# Fri3d_2024_Blaster_01.net
KiCad netlist of a schematic drawn in Altium Designer
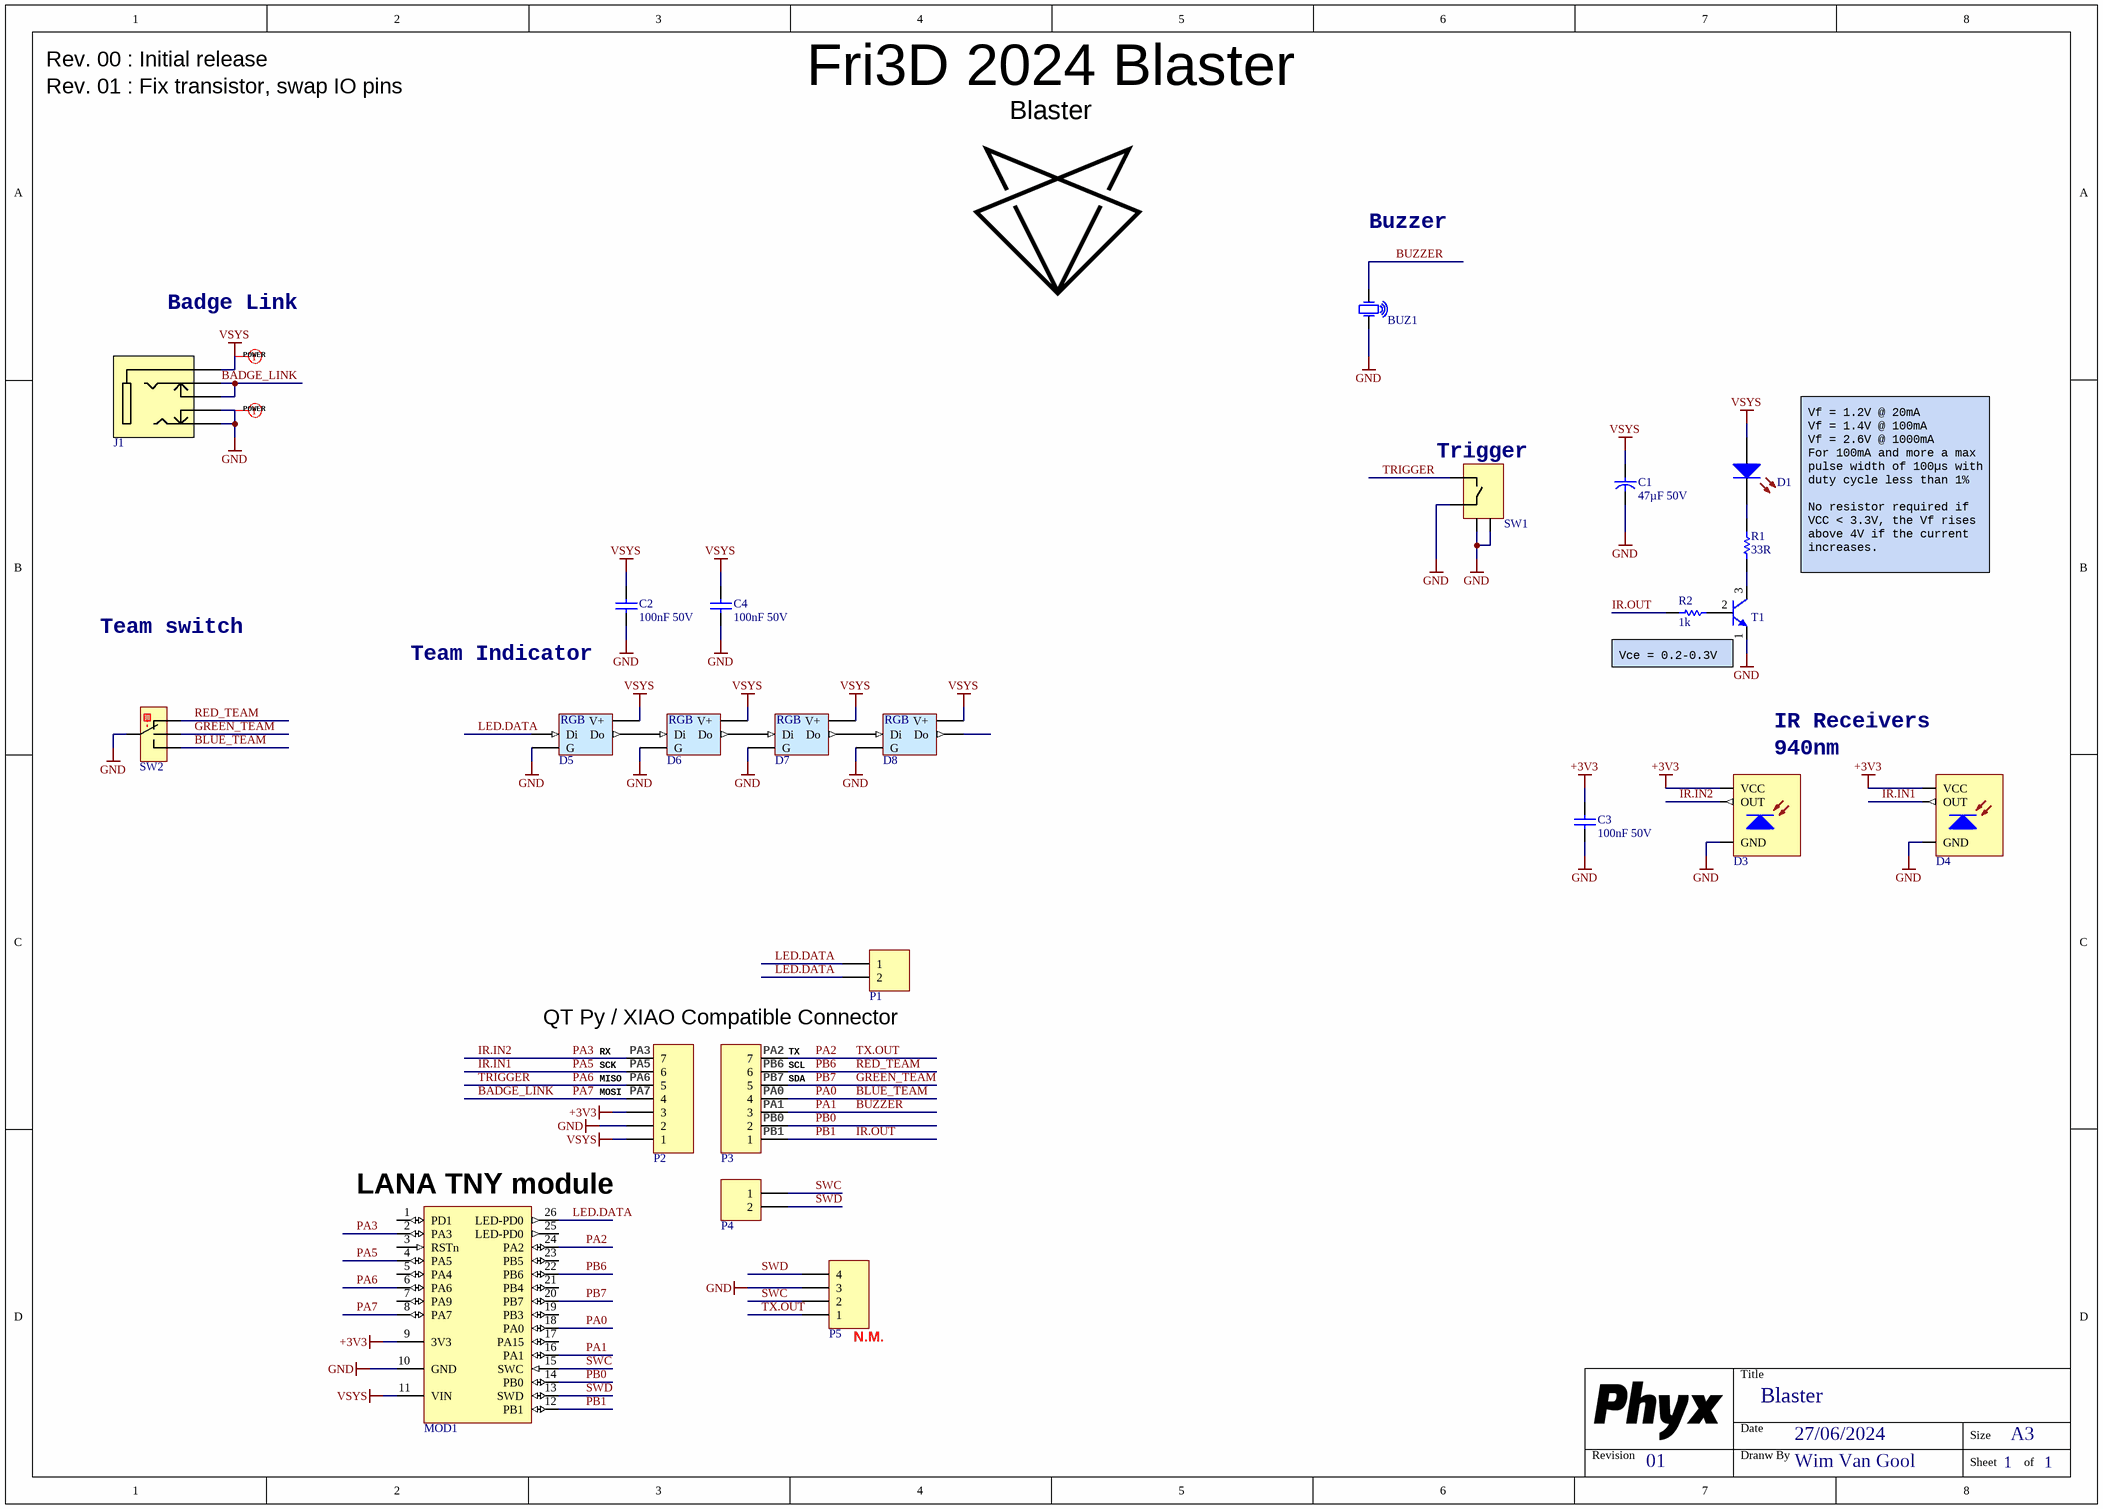
[diagram p0: Fri3d_2024_Blaster_01.SchDoc]

(export (version "E")
  (design (tool "Eeschema 10.0.6"))
  (components
    (comp (ref "BUZ1")
      (value "14x14x7mm Piezo Buzzer Transducer 80dB")
      (footprint "CUI_CEP-1162")
      (description "Crystal Oscillator")
      (libsource (lib "Phyx_Components") (part "Buzzer"))
    )
    (comp (ref "C1")
      (value "47µF 50V")
      (footprint "C_8x9_3.5mm")
      (description "Capacitor electrolyt")
      (fields (field (name "Comment") "CAP_POL"))
      (libsource (lib "Phyx_Components") (part "CAP_POL"))
    )
    (comp (ref "C2")
      (value "100nF 50V")
      (footprint "C_5.08mm")
      (description "Capacitor Ceramic")
      (fields (field (name "Comment") "CAP_CERAMIC"))
      (libsource (lib "Phyx_Components") (part "CAP_CERAMIC"))
    )
    (comp (ref "C3")
      (value "100nF 50V")
      (footprint "C_5.08mm")
      (description "Capacitor Ceramic")
      (fields (field (name "Comment") "CAP_CERAMIC"))
      (libsource (lib "Phyx_Components") (part "CAP_CERAMIC"))
    )
    (comp (ref "C4")
      (value "100nF 50V")
      (footprint "C_5.08mm")
      (description "Capacitor Ceramic")
      (fields (field (name "Comment") "CAP_CERAMIC"))
      (libsource (lib "Phyx_Components") (part "CAP_CERAMIC"))
    )
    (comp (ref "D1")
      (value "5mm IR LED, 940nm, 100mA, 1.35V, 25Deg")
      (footprint "LED_5MM_RD")
      (description "=Description")
      (libsource (lib "Phyx_Components") (part "LED_IR"))
    )
    (comp (ref "D3")
      (value "IRM-3638N3F14 Infrared Receiver 38 kHz 45° 2.7-5.5V")
      (footprint "VIS_TSOP381x_BENT")
      (description "=Description")
      (libsource (lib "Phyx_Components") (part "PHO_IR_TSOP381x"))
    )
    (comp (ref "D4")
      (value "IRM-3638N3F14 Infrared Receiver 38 kHz 45° 2.7-5.5V")
      (footprint "VIS_TSOP381x_BENT")
      (description "=Description")
      (libsource (lib "Phyx_Components") (part "PHO_IR_TSOP381x"))
    )
    (comp (ref "D5")
      (value "WS2812 based digital RGB LED 4020 White package Side emitting")
      (footprint "LED_8mm_RGB_RA_EASY")
      (description "=Description")
      (libsource (lib "Phyx_Components") (part "LED_RGB_WS2812B_5mm"))
    )
    (comp (ref "D6")
      (value "WS2812 based digital RGB LED 4020 White package Side emitting")
      (footprint "LED_8mm_RGB_RA_EASY")
      (description "=Description")
      (libsource (lib "Phyx_Components") (part "LED_RGB_WS2812B_5mm"))
    )
    (comp (ref "D7")
      (value "WS2812 based digital RGB LED 4020 White package Side emitting")
      (footprint "LED_8mm_RGB_RA_EASY")
      (description "=Description")
      (libsource (lib "Phyx_Components") (part "LED_RGB_WS2812B_5mm"))
    )
    (comp (ref "D8")
      (value "WS2812 based digital RGB LED 4020 White package Side emitting")
      (footprint "LED_8mm_RGB_RA_EASY")
      (description "=Description")
      (libsource (lib "Phyx_Components") (part "LED_RGB_WS2812B_5mm"))
    )
    (comp (ref "J1")
      (value "3.5mm jack, dual switch, black, 3 contacts")
      (footprint "CUI_SJ1-3525NG")
      (description "=Description")
      (libsource (lib "Phyx_Components") (part "CUI_SJ1-3525NG"))
    )
    (comp (ref "MOD1")
      (value "CH23V203 based TNY module")
      (footprint "PHYX_LANA_TNY_SMD")
      (libsource (lib "Phyx_Components") (part "PHYX_LANA_TNY_SMD"))
    )
    (comp (ref "P1")
      (value "Header 2")
      (footprint "HDR1X2")
      (libsource (lib "Phyx_Components") (part "Header 2"))
    )
    (comp (ref "P2")
      (value "Header 7")
      (footprint "HDR1X7")
      (libsource (lib "Phyx_Components") (part "Header 7"))
    )
    (comp (ref "P3") (value "Header 7") (footprint "HDR1X7") (libsource (lib "") (part "Header 7_1")))
    (comp (ref "P4") (value "Header 2") (footprint "HDR1X2") (libsource (lib "") (part "Header 2_1")))
    (comp (ref "P5")
      (value "Header 4")
      (footprint "HDR1X4")
      (libsource (lib "Phyx_Components") (part "Header 4"))
    )
    (comp (ref "R1")
      (value "33R")
      (footprint "RES_10mm")
      (fields (field (name "Comment") "RESISTOR"))
      (libsource (lib "Phyx_Components") (part "RESISTOR"))
    )
    (comp (ref "R2")
      (value "1k")
      (footprint "RES_10mm")
      (fields (field (name "Comment") "RESISTOR"))
      (libsource (lib "Phyx_Components") (part "RESISTOR"))
    )
    (comp (ref "SW1")
      (value "Tact switch, RA, 3,85mm")
      (footprint "TACTSW_RA_385")
      (libsource (lib "Phyx_Components") (part "SW_TACT_RA"))
    )
    (comp (ref "SW2")
      (value "1P3T SK13D07VG3 3mm post")
      (footprint "SK13D07VG3")
      (libsource (lib "Phyx_Components") (part "SW_1P3T"))
    )
    (comp (ref "T1")
      (value "0.2A 40V 100hfe NPN Transistor")
      (footprint "TO-92A_WIDE")
      (libsource (lib "Phyx_Components") (part "NPN_EBC"))
    )
  )
  (nets
    (net (code "1") (name "+3V3") (class "Default")
      (node (ref "C3") (pin "1") (pinfunction "1_1") (pintype "passive"))
      (node (ref "D3") (pin "3") (pinfunction "VCC_3") (pintype "power_in"))
      (node (ref "D4") (pin "3") (pinfunction "VCC_3") (pintype "power_in"))
      (node (ref "MOD1") (pin "9") (pinfunction "3V3_9") (pintype "power_in"))
      (node (ref "P2") (pin "3") (pinfunction "3_3") (pintype "passive"))
    )
    (net (code "3") (name "/BADGE_LINK") (class "Default")
      (node (ref "J1") (pin "3") (pinfunction "Ring_3") (pintype "passive"))
      (node (ref "J1") (pin "5") (pinfunction "5_5") (pintype "passive"))
      (node (ref "MOD1") (pin "8") (pinfunction "PA7_8") (pintype "bidirectional"))
      (node (ref "P2") (pin "4") (pinfunction "4_4") (pintype "passive"))
    )
    (net (code "4") (name "/BLUE_TEAM") (class "Default")
      (node (ref "MOD1") (pin "18") (pinfunction "PA0_18") (pintype "bidirectional"))
      (node (ref "P3") (pin "4") (pinfunction "4_4") (pintype "passive"))
      (node (ref "SW2") (pin "4") (pinfunction "4_4") (pintype "passive"))
    )
    (net (code "5") (name "/BUZZER") (class "Default")
      (node (ref "BUZ1") (pin "2") (pinfunction "OSC2_2") (pintype "passive"))
      (node (ref "MOD1") (pin "16") (pinfunction "PA1_16") (pintype "bidirectional"))
      (node (ref "P3") (pin "3") (pinfunction "3_3") (pintype "passive"))
    )
    (net (code "6") (name "/GREEN_TEAM") (class "Default")
      (node (ref "MOD1") (pin "20") (pinfunction "PB7_20") (pintype "bidirectional"))
      (node (ref "P3") (pin "5") (pinfunction "5_5") (pintype "passive"))
      (node (ref "SW2") (pin "2") (pinfunction "2_2") (pintype "passive"))
    )
    (net (code "7") (name "/IR.IN1") (class "Default")
      (node (ref "D4") (pin "1") (pinfunction "OUT_1") (pintype "output"))
      (node (ref "MOD1") (pin "4") (pinfunction "PA5_4") (pintype "bidirectional"))
      (node (ref "P2") (pin "6") (pinfunction "6_6") (pintype "passive"))
    )
    (net (code "8") (name "/IR.IN2") (class "Default")
      (node (ref "D3") (pin "1") (pinfunction "OUT_1") (pintype "output"))
      (node (ref "MOD1") (pin "2") (pinfunction "PA3_2") (pintype "bidirectional"))
      (node (ref "P2") (pin "7") (pinfunction "7_7") (pintype "passive"))
    )
    (net (code "9") (name "/IR.OUT") (class "Default")
      (node (ref "MOD1") (pin "12") (pinfunction "PB1_12") (pintype "bidirectional"))
      (node (ref "P3") (pin "1") (pinfunction "1_1") (pintype "passive"))
      (node (ref "R2") (pin "2") (pinfunction "2_2") (pintype "passive"))
    )
    (net (code "10") (name "/LED.DATA") (class "Default")
      (node (ref "D5") (pin "4") (pinfunction "Di_4") (pintype "input"))
      (node (ref "MOD1") (pin "26") (pinfunction "LED-PD0_26") (pintype "output"))
      (node (ref "P1") (pin "1") (pinfunction "1_1") (pintype "passive"))
      (node (ref "P1") (pin "2") (pinfunction "2_2") (pintype "passive"))
    )
    (net (code "11") (name "/PA2") (class "Default")
      (node (ref "MOD1") (pin "24") (pinfunction "PA2_24") (pintype "bidirectional"))
      (node (ref "P3") (pin "7") (pinfunction "7_7") (pintype "passive"))
      (node (ref "P5") (pin "1") (pinfunction "1_1") (pintype "passive"))
    )
    (net (code "12") (name "/PA6") (class "Default")
      (node (ref "MOD1") (pin "6") (pinfunction "PA6_6") (pintype "bidirectional"))
      (node (ref "P2") (pin "5") (pinfunction "5_5") (pintype "passive"))
      (node (ref "SW1") (pin "1") (pinfunction "1_1") (pintype "passive"))
    )
    (net (code "13") (name "/PB0") (class "Default")
      (node (ref "MOD1") (pin "14") (pinfunction "PB0_14") (pintype "bidirectional"))
      (node (ref "P3") (pin "2") (pinfunction "2_2") (pintype "passive"))
    )
    (net (code "14") (name "/PB6") (class "Default")
      (node (ref "MOD1") (pin "22") (pinfunction "PB6_22") (pintype "bidirectional"))
      (node (ref "P3") (pin "6") (pinfunction "6_6") (pintype "passive"))
      (node (ref "SW2") (pin "1") (pinfunction "1_1") (pintype "passive"))
    )
    (net (code "15") (name "/SWC") (class "Default")
      (node (ref "MOD1") (pin "15") (pinfunction "SWC_15") (pintype "input"))
      (node (ref "P4") (pin "1") (pinfunction "1_1") (pintype "passive"))
      (node (ref "P5") (pin "2") (pinfunction "2_2") (pintype "passive"))
    )
    (net (code "16") (name "/SWD") (class "Default")
      (node (ref "MOD1") (pin "13") (pinfunction "SWD_13") (pintype "bidirectional"))
      (node (ref "P4") (pin "2") (pinfunction "2_2") (pintype "passive"))
      (node (ref "P5") (pin "4") (pinfunction "4_4") (pintype "passive"))
    )
    (net (code "17") (name "GND") (class "Default")
      (node (ref "BUZ1") (pin "1") (pinfunction "OSC1_1") (pintype "passive"))
      (node (ref "C1") (pin "2") (pinfunction "2_2") (pintype "passive"))
      (node (ref "C2") (pin "2") (pinfunction "2_2") (pintype "passive"))
      (node (ref "C3") (pin "2") (pinfunction "2_2") (pintype "passive"))
      (node (ref "C4") (pin "2") (pinfunction "2_2") (pintype "passive"))
      (node (ref "D3") (pin "2") (pinfunction "GND_2") (pintype "power_in"))
      (node (ref "D4") (pin "2") (pinfunction "GND_2") (pintype "power_in"))
      (node (ref "D5") (pin "3") (pinfunction "G_3") (pintype "power_in"))
      (node (ref "D6") (pin "3") (pinfunction "G_3") (pintype "power_in"))
      (node (ref "D7") (pin "3") (pinfunction "G_3") (pintype "power_in"))
      (node (ref "D8") (pin "3") (pinfunction "G_3") (pintype "power_in"))
      (node (ref "J1") (pin "2") (pinfunction "Tip_2") (pintype "passive"))
      (node (ref "J1") (pin "4") (pinfunction "4_4") (pintype "passive"))
      (node (ref "MOD1") (pin "10") (pinfunction "GND_10") (pintype "power_in"))
      (node (ref "P2") (pin "2") (pinfunction "2_2") (pintype "passive"))
      (node (ref "P5") (pin "3") (pinfunction "3_3") (pintype "passive"))
      (node (ref "SW1") (pin "2") (pinfunction "2_2") (pintype "passive"))
      (node (ref "SW1") (pin "MH1") (pinfunction "MH1_MH1") (pintype "passive"))
      (node (ref "SW1") (pin "MH2") (pinfunction "MH2_MH2") (pintype "passive"))
      (node (ref "SW2") (pin "3") (pinfunction "3_3") (pintype "passive"))
      (node (ref "T1") (pin "1") (pinfunction "C_1") (pintype "passive"))
    )
    (net (code "18") (name "Net-(D1-K)") (class "Default")
      (node (ref "D1") (pin "2") (pinfunction "K_2") (pintype "passive"))
      (node (ref "R1") (pin "1") (pinfunction "1_1") (pintype "passive"))
    )
    (net (code "19") (name "Net-(D5-Do)") (class "Default")
      (node (ref "D5") (pin "1") (pinfunction "Do_1") (pintype "output"))
      (node (ref "D6") (pin "4") (pinfunction "Di_4") (pintype "input"))
    )
    (net (code "20") (name "Net-(D6-Do)") (class "Default")
      (node (ref "D6") (pin "1") (pinfunction "Do_1") (pintype "output"))
      (node (ref "D7") (pin "4") (pinfunction "Di_4") (pintype "input"))
    )
    (net (code "21") (name "Net-(D7-Do)") (class "Default")
      (node (ref "D7") (pin "1") (pinfunction "Do_1") (pintype "output"))
      (node (ref "D8") (pin "4") (pinfunction "Di_4") (pintype "input"))
    )
    (net (code "22") (name "Net-(T1-B)") (class "Default")
      (node (ref "R2") (pin "1") (pinfunction "1_1") (pintype "passive"))
      (node (ref "T1") (pin "2") (pinfunction "B_2") (pintype "passive"))
    )
    (net (code "23") (name "Net-(T1-E)") (class "Default")
      (node (ref "R1") (pin "2") (pinfunction "2_2") (pintype "passive"))
      (node (ref "T1") (pin "3") (pinfunction "E_3") (pintype "passive"))
    )
    (net (code "24") (name "VSYS") (class "Default")
      (node (ref "C1") (pin "1") (pinfunction "1_1") (pintype "passive"))
      (node (ref "C2") (pin "1") (pinfunction "1_1") (pintype "passive"))
      (node (ref "C4") (pin "1") (pinfunction "1_1") (pintype "passive"))
      (node (ref "D1") (pin "1") (pinfunction "A_1") (pintype "passive"))
      (node (ref "D5") (pin "2") (pinfunction "V+_2") (pintype "power_in"))
      (node (ref "D6") (pin "2") (pinfunction "V+_2") (pintype "power_in"))
      (node (ref "D7") (pin "2") (pinfunction "V+_2") (pintype "power_in"))
      (node (ref "D8") (pin "2") (pinfunction "V+_2") (pintype "power_in"))
      (node (ref "J1") (pin "1") (pinfunction "Sleeve_1") (pintype "passive"))
      (node (ref "MOD1") (pin "11") (pinfunction "VIN_11") (pintype "power_in"))
      (node (ref "P2") (pin "1") (pinfunction "1_1") (pintype "passive"))
    )
    (net (code "25") (name "unconnected-(D8-Do-Pad1)") (class "Default")
      (node (ref "D8") (pin "1") (pinfunction "Do_1") (pintype "output"))
    )
    (net (code "26") (name "unconnected-(MOD1-LED-PD0-Pad25)") (class "Default")
      (node (ref "MOD1") (pin "25") (pinfunction "LED-PD0_25") (pintype "output"))
    )
    (net (code "27") (name "unconnected-(MOD1-PA4-Pad5)") (class "Default")
      (node (ref "MOD1") (pin "5") (pinfunction "PA4_5") (pintype "bidirectional"))
    )
    (net (code "28") (name "unconnected-(MOD1-PA9-Pad7)") (class "Default")
      (node (ref "MOD1") (pin "7") (pinfunction "PA9_7") (pintype "bidirectional"))
    )
    (net (code "29") (name "unconnected-(MOD1-PA15-Pad17)") (class "Default")
      (node (ref "MOD1") (pin "17") (pinfunction "PA15_17") (pintype "bidirectional"))
    )
    (net (code "30") (name "unconnected-(MOD1-PB3-Pad19)") (class "Default")
      (node (ref "MOD1") (pin "19") (pinfunction "PB3_19") (pintype "bidirectional"))
    )
    (net (code "31") (name "unconnected-(MOD1-PB4-Pad21)") (class "Default")
      (node (ref "MOD1") (pin "21") (pinfunction "PB4_21") (pintype "bidirectional"))
    )
    (net (code "32") (name "unconnected-(MOD1-PB5-Pad23)") (class "Default")
      (node (ref "MOD1") (pin "23") (pinfunction "PB5_23") (pintype "bidirectional"))
    )
    (net (code "33") (name "unconnected-(MOD1-PD1-Pad1)") (class "Default")
      (node (ref "MOD1") (pin "1") (pinfunction "PD1_1") (pintype "bidirectional"))
    )
    (net (code "34") (name "unconnected-(MOD1-RSTn-Pad3)") (class "Default")
      (node (ref "MOD1") (pin "3") (pinfunction "RSTn_3") (pintype "input"))
    )
  )
)
